# MCU_Power.net
KiCad netlist of a schematic drawn in Altium Designer
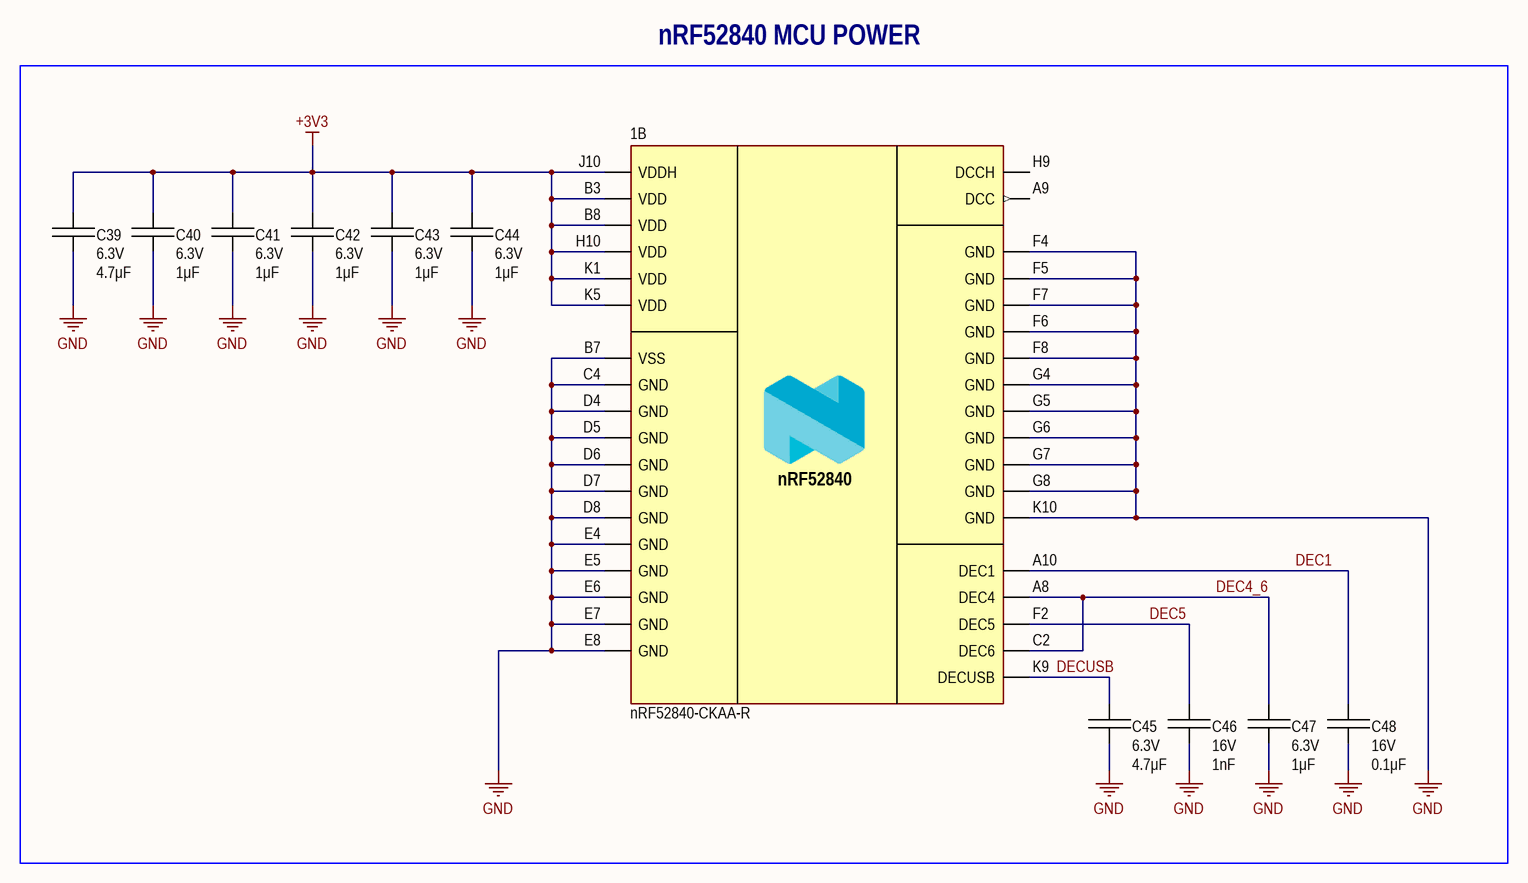
[diagram p0: MCU_Power.SchDoc]

(export (version "E")
  (design (tool "Eeschema 10.0.6"))
  (components
    (comp (ref "1")
      (value "~")
      (footprint "MCU: nRF52840_WLCP93")
      (description "MCU")
      (fields
        (field (name "MANUFACTURER") "Nordic Semiconductor")
        (field (name "VALUEMANUFACTURERPARTNUMBER") "IC microcontroller, 32bit, Cortex-M4, 64 MHz, 1 MB, 256 kB, , , 93-WLCSP")
        (field (name "PARTNUMBER") "nRF52840-CKAA-R")
      )
      (libsource (lib "MyLib") (part "nRF52840"))
    )
    (comp (ref "C39")
      (value "4.7μF")
      (footprint "CAP: 0603_NO_SILK")
      (description "4.7 µF ±20% 6.3V Ceramic Capacitor X7R 0603 (1608 Metric)")
      (fields
        (field (name "MANUFACTURER") "Yageo")
        (field (name "PARTNUMBER") "CC0603MRX7R5BB475")
        (field (name "VOLTAGE") "6.3V")
      )
      (libsource (lib "capacitor") (part "Ceramic_0603"))
    )
    (comp (ref "C40")
      (value "1μF")
      (footprint "CAP: 0402_NO_SILK")
      (description "1 µF ±10% 6.3V Ceramic Capacitor X7R 0402 (1005 Metric)")
      (fields
        (field (name "MANUFACTURER") "Yageo")
        (field (name "PARTNUMBER") "CC0402KRX7R5BB105")
        (field (name "VOLTAGE") "6.3V")
      )
      (libsource (lib "capacitor") (part "Ceramic_0402"))
    )
    (comp (ref "C41")
      (value "1μF")
      (footprint "CAP: 0402_NO_SILK")
      (description "1 µF ±10% 6.3V Ceramic Capacitor X7R 0402 (1005 Metric)")
      (fields
        (field (name "MANUFACTURER") "Yageo")
        (field (name "PARTNUMBER") "CC0402KRX7R5BB105")
        (field (name "VOLTAGE") "6.3V")
      )
      (libsource (lib "capacitor") (part "Ceramic_0402"))
    )
    (comp (ref "C42")
      (value "1μF")
      (footprint "CAP: 0402_NO_SILK")
      (description "1 µF ±10% 6.3V Ceramic Capacitor X7R 0402 (1005 Metric)")
      (fields
        (field (name "MANUFACTURER") "Yageo")
        (field (name "PARTNUMBER") "CC0402KRX7R5BB105")
        (field (name "VOLTAGE") "6.3V")
      )
      (libsource (lib "capacitor") (part "Ceramic_0402"))
    )
    (comp (ref "C43")
      (value "1μF")
      (footprint "CAP: 0402_NO_SILK")
      (description "1 µF ±10% 6.3V Ceramic Capacitor X7R 0402 (1005 Metric)")
      (fields
        (field (name "MANUFACTURER") "Yageo")
        (field (name "PARTNUMBER") "CC0402KRX7R5BB105")
        (field (name "VOLTAGE") "6.3V")
      )
      (libsource (lib "capacitor") (part "Ceramic_0402"))
    )
    (comp (ref "C44")
      (value "1μF")
      (footprint "CAP: 0402_NO_SILK")
      (description "1 µF ±10% 6.3V Ceramic Capacitor X7R 0402 (1005 Metric)")
      (fields
        (field (name "MANUFACTURER") "Yageo")
        (field (name "PARTNUMBER") "CC0402KRX7R5BB105")
        (field (name "VOLTAGE") "6.3V")
      )
      (libsource (lib "capacitor") (part "Ceramic_0402"))
    )
    (comp (ref "C45")
      (value "4.7μF")
      (footprint "CAP: 0603_NO_SILK")
      (description "4.7 µF ±20% 6.3V Ceramic Capacitor X7R 0603 (1608 Metric)")
      (fields
        (field (name "MANUFACTURER") "Yageo")
        (field (name "PARTNUMBER") "CC0603MRX7R5BB475")
        (field (name "VOLTAGE") "6.3V")
      )
      (libsource (lib "capacitor") (part "Ceramic_0603"))
    )
    (comp (ref "C46")
      (value "1nF")
      (footprint "CAP: 0201")
      (description "1000 pF ±10% 16V Ceramic Capacitor X7R 0201 (0603 Metric)")
      (fields
        (field (name "MANUFACTURER") "Yageo")
        (field (name "PARTNUMBER") "CC0201KRX7R7BB102")
        (field (name "VOLTAGE") "16V")
      )
      (libsource (lib "capacitor") (part "Ceramic_0201"))
    )
    (comp (ref "C47")
      (value "1μF")
      (footprint "CAP: 0402_NO_SILK")
      (description "1 µF ±10% 6.3V Ceramic Capacitor X7R 0402 (1005 Metric)")
      (fields
        (field (name "MANUFACTURER") "Yageo")
        (field (name "PARTNUMBER") "CC0402KRX7R5BB105")
        (field (name "VOLTAGE") "6.3V")
      )
      (libsource (lib "capacitor") (part "Ceramic_0402"))
    )
    (comp (ref "C48")
      (value "0.1μF")
      (footprint "CAP: 0402_NO_SILK")
      (description "0.1 µF ±10% 16V Ceramic Capacitor X7R 0402 (1005 Metric)")
      (fields
        (field (name "MANUFACTURER") "Yageo")
        (field (name "PARTNUMBER") "CC0402KRX7R7BB104")
        (field (name "VOLTAGE") "16V")
      )
      (libsource (lib "capacitor") (part "Ceramic_0402"))
    )
  )
  (nets
    (net (code "1") (name "+3V3") (class "Default")
      (node (ref "1") (pin "B3") (pinfunction "VDD_B3") (pintype "power_in"))
      (node (ref "1") (pin "B8") (pinfunction "VDD_B8") (pintype "power_in"))
      (node (ref "1") (pin "H10") (pinfunction "VDD_H10") (pintype "power_in"))
      (node (ref "1") (pin "J10") (pinfunction "VDDH_J10") (pintype "power_in"))
      (node (ref "1") (pin "K1") (pinfunction "VDD_K1") (pintype "power_in"))
      (node (ref "1") (pin "K5") (pinfunction "VDD_K5") (pintype "power_in"))
      (node (ref "C39") (pin "2") (pinfunction "2_2") (pintype "passive"))
      (node (ref "C40") (pin "2") (pinfunction "2_2") (pintype "passive"))
      (node (ref "C41") (pin "2") (pinfunction "2_2") (pintype "passive"))
      (node (ref "C42") (pin "2") (pinfunction "2_2") (pintype "passive"))
      (node (ref "C43") (pin "2") (pinfunction "2_2") (pintype "passive"))
      (node (ref "C44") (pin "2") (pinfunction "2_2") (pintype "passive"))
    )
    (net (code "2") (name "/DEC1") (class "Default")
      (node (ref "1") (pin "A10") (pinfunction "DEC1_A10") (pintype "power_in"))
      (node (ref "C48") (pin "2") (pinfunction "2_2") (pintype "passive"))
    )
    (net (code "3") (name "/DEC4_6") (class "Default")
      (node (ref "1") (pin "A8") (pinfunction "DEC4_A8") (pintype "power_in"))
      (node (ref "1") (pin "C2") (pinfunction "DEC6_C2") (pintype "power_in"))
      (node (ref "C47") (pin "2") (pinfunction "2_2") (pintype "passive"))
    )
    (net (code "4") (name "/DEC5") (class "Default")
      (node (ref "1") (pin "F2") (pinfunction "DEC5_F2") (pintype "power_in"))
      (node (ref "C46") (pin "2") (pinfunction "2_2") (pintype "passive"))
    )
    (net (code "5") (name "/DECUSB") (class "Default")
      (node (ref "1") (pin "K9") (pinfunction "DECUSB_K9") (pintype "power_in"))
      (node (ref "C45") (pin "2") (pinfunction "2_2") (pintype "passive"))
    )
    (net (code "6") (name "GND") (class "Default")
      (node (ref "1") (pin "B7") (pinfunction "VSS_B7") (pintype "power_in"))
      (node (ref "1") (pin "C4") (pinfunction "GND_C4") (pintype "power_in"))
      (node (ref "1") (pin "D4") (pinfunction "GND_D4") (pintype "power_in"))
      (node (ref "1") (pin "D5") (pinfunction "GND_D5") (pintype "power_in"))
      (node (ref "1") (pin "D6") (pinfunction "GND_D6") (pintype "power_in"))
      (node (ref "1") (pin "D7") (pinfunction "GND_D7") (pintype "power_in"))
      (node (ref "1") (pin "D8") (pinfunction "GND_D8") (pintype "power_in"))
      (node (ref "1") (pin "E4") (pinfunction "GND_E4") (pintype "power_in"))
      (node (ref "1") (pin "E5") (pinfunction "GND_E5") (pintype "power_in"))
      (node (ref "1") (pin "E6") (pinfunction "GND_E6") (pintype "power_in"))
      (node (ref "1") (pin "E7") (pinfunction "GND_E7") (pintype "power_in"))
      (node (ref "1") (pin "E8") (pinfunction "GND_E8") (pintype "power_in"))
      (node (ref "1") (pin "F4") (pinfunction "GND_F4") (pintype "power_in"))
      (node (ref "1") (pin "F5") (pinfunction "GND_F5") (pintype "power_in"))
      (node (ref "1") (pin "F6") (pinfunction "GND_F6") (pintype "power_in"))
      (node (ref "1") (pin "F7") (pinfunction "GND_F7") (pintype "power_in"))
      (node (ref "1") (pin "F8") (pinfunction "GND_F8") (pintype "power_in"))
      (node (ref "1") (pin "G4") (pinfunction "GND_G4") (pintype "power_in"))
      (node (ref "1") (pin "G5") (pinfunction "GND_G5") (pintype "power_in"))
      (node (ref "1") (pin "G6") (pinfunction "GND_G6") (pintype "power_in"))
      (node (ref "1") (pin "G7") (pinfunction "GND_G7") (pintype "power_in"))
      (node (ref "1") (pin "G8") (pinfunction "GND_G8") (pintype "power_in"))
      (node (ref "1") (pin "K10") (pinfunction "GND_K10") (pintype "power_in"))
      (node (ref "C39") (pin "1") (pinfunction "1_1") (pintype "passive"))
      (node (ref "C40") (pin "1") (pinfunction "1_1") (pintype "passive"))
      (node (ref "C41") (pin "1") (pinfunction "1_1") (pintype "passive"))
      (node (ref "C42") (pin "1") (pinfunction "1_1") (pintype "passive"))
      (node (ref "C43") (pin "1") (pinfunction "1_1") (pintype "passive"))
      (node (ref "C44") (pin "1") (pinfunction "1_1") (pintype "passive"))
      (node (ref "C45") (pin "1") (pinfunction "1_1") (pintype "passive"))
      (node (ref "C46") (pin "1") (pinfunction "1_1") (pintype "passive"))
      (node (ref "C47") (pin "1") (pinfunction "1_1") (pintype "passive"))
      (node (ref "C48") (pin "1") (pinfunction "1_1") (pintype "passive"))
    )
    (net (code "7") (name "unconnected-(1B-DCC-PadA9)") (class "Default")
      (node (ref "1") (pin "A9") (pinfunction "DCC_A9") (pintype "output"))
    )
    (net (code "8") (name "unconnected-(1B-DCCH-PadH9)") (class "Default")
      (node (ref "1") (pin "H9") (pinfunction "DCCH_H9") (pintype "power_in"))
    )
  )
)
